# powerSMALL_smaller_OUT_GND.net
KiCad netlist of a schematic drawn in EAGLE
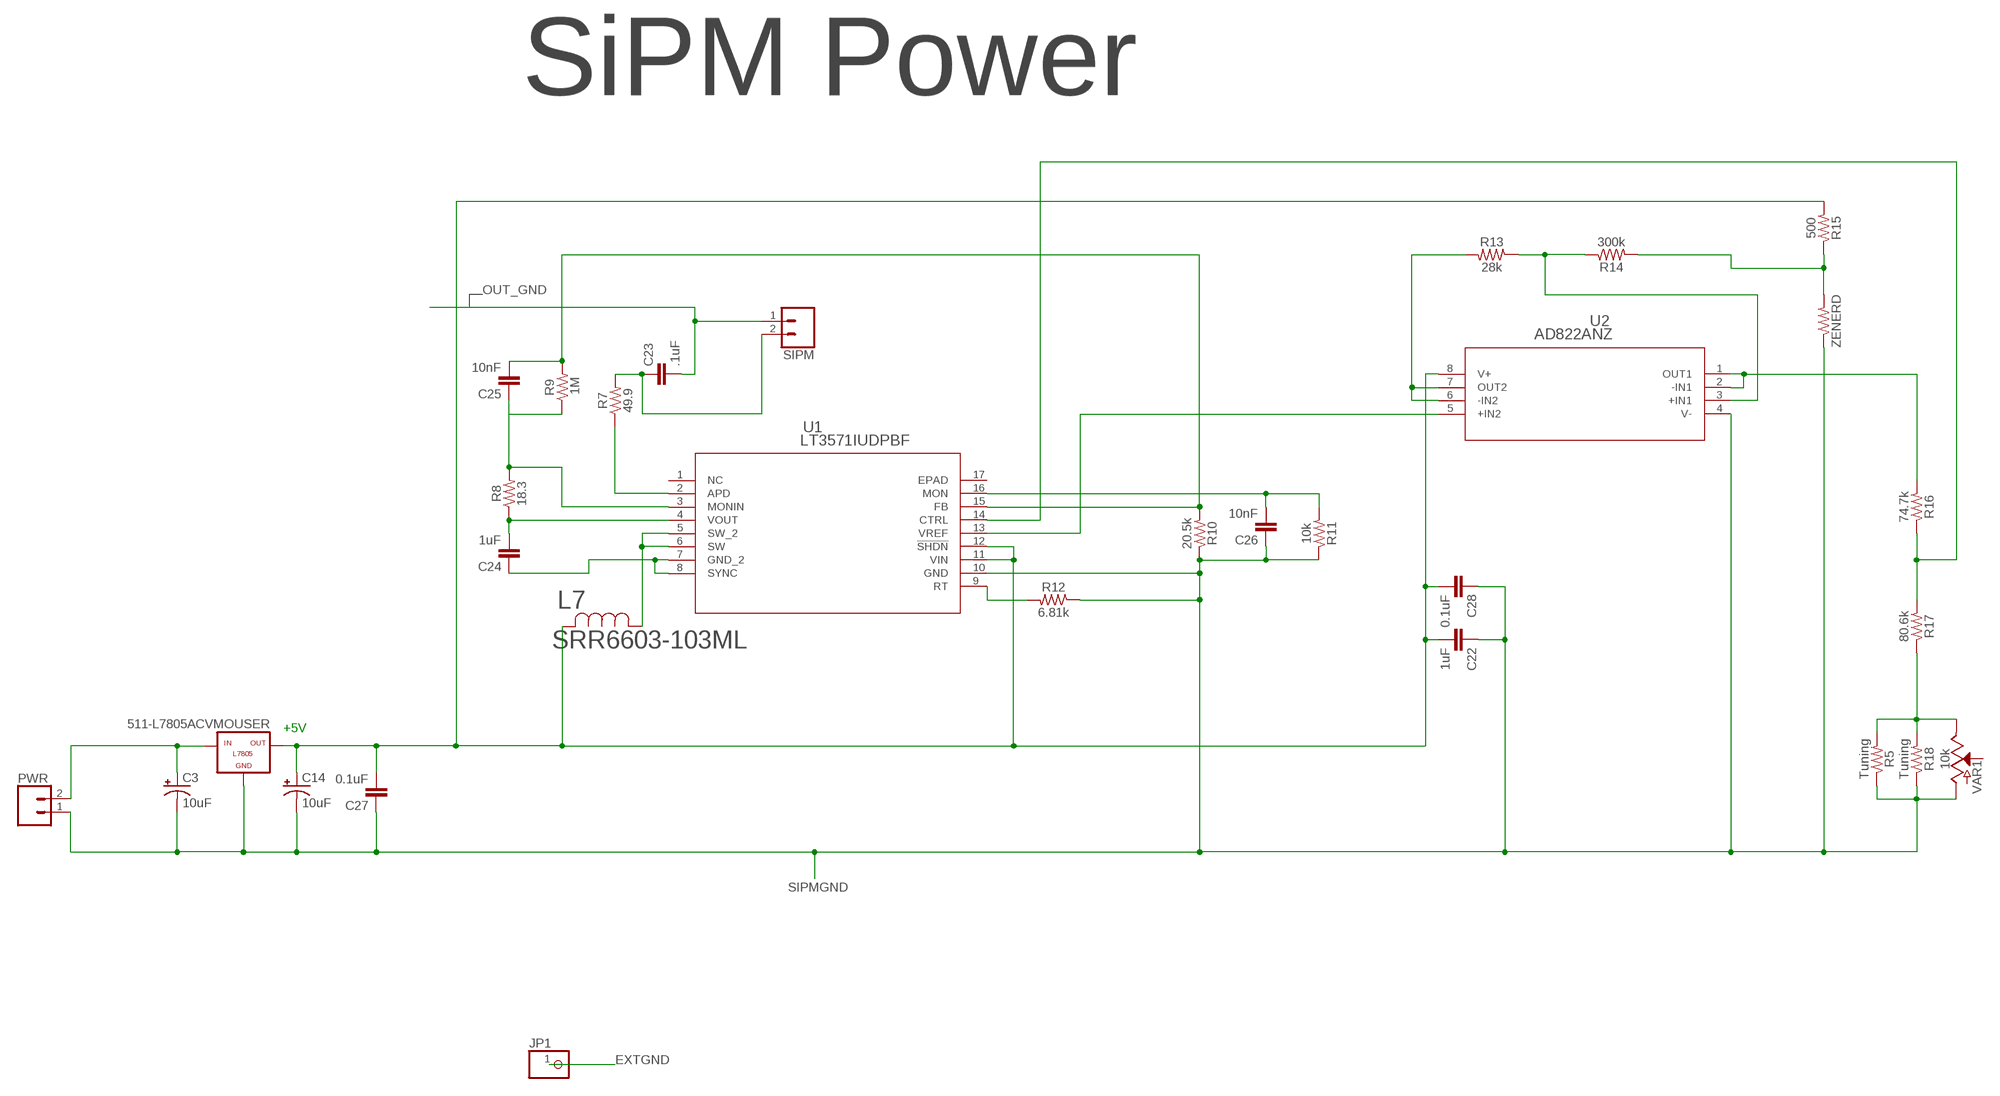
[diagram p0: schematic, sheet 1, part 1 of 2]
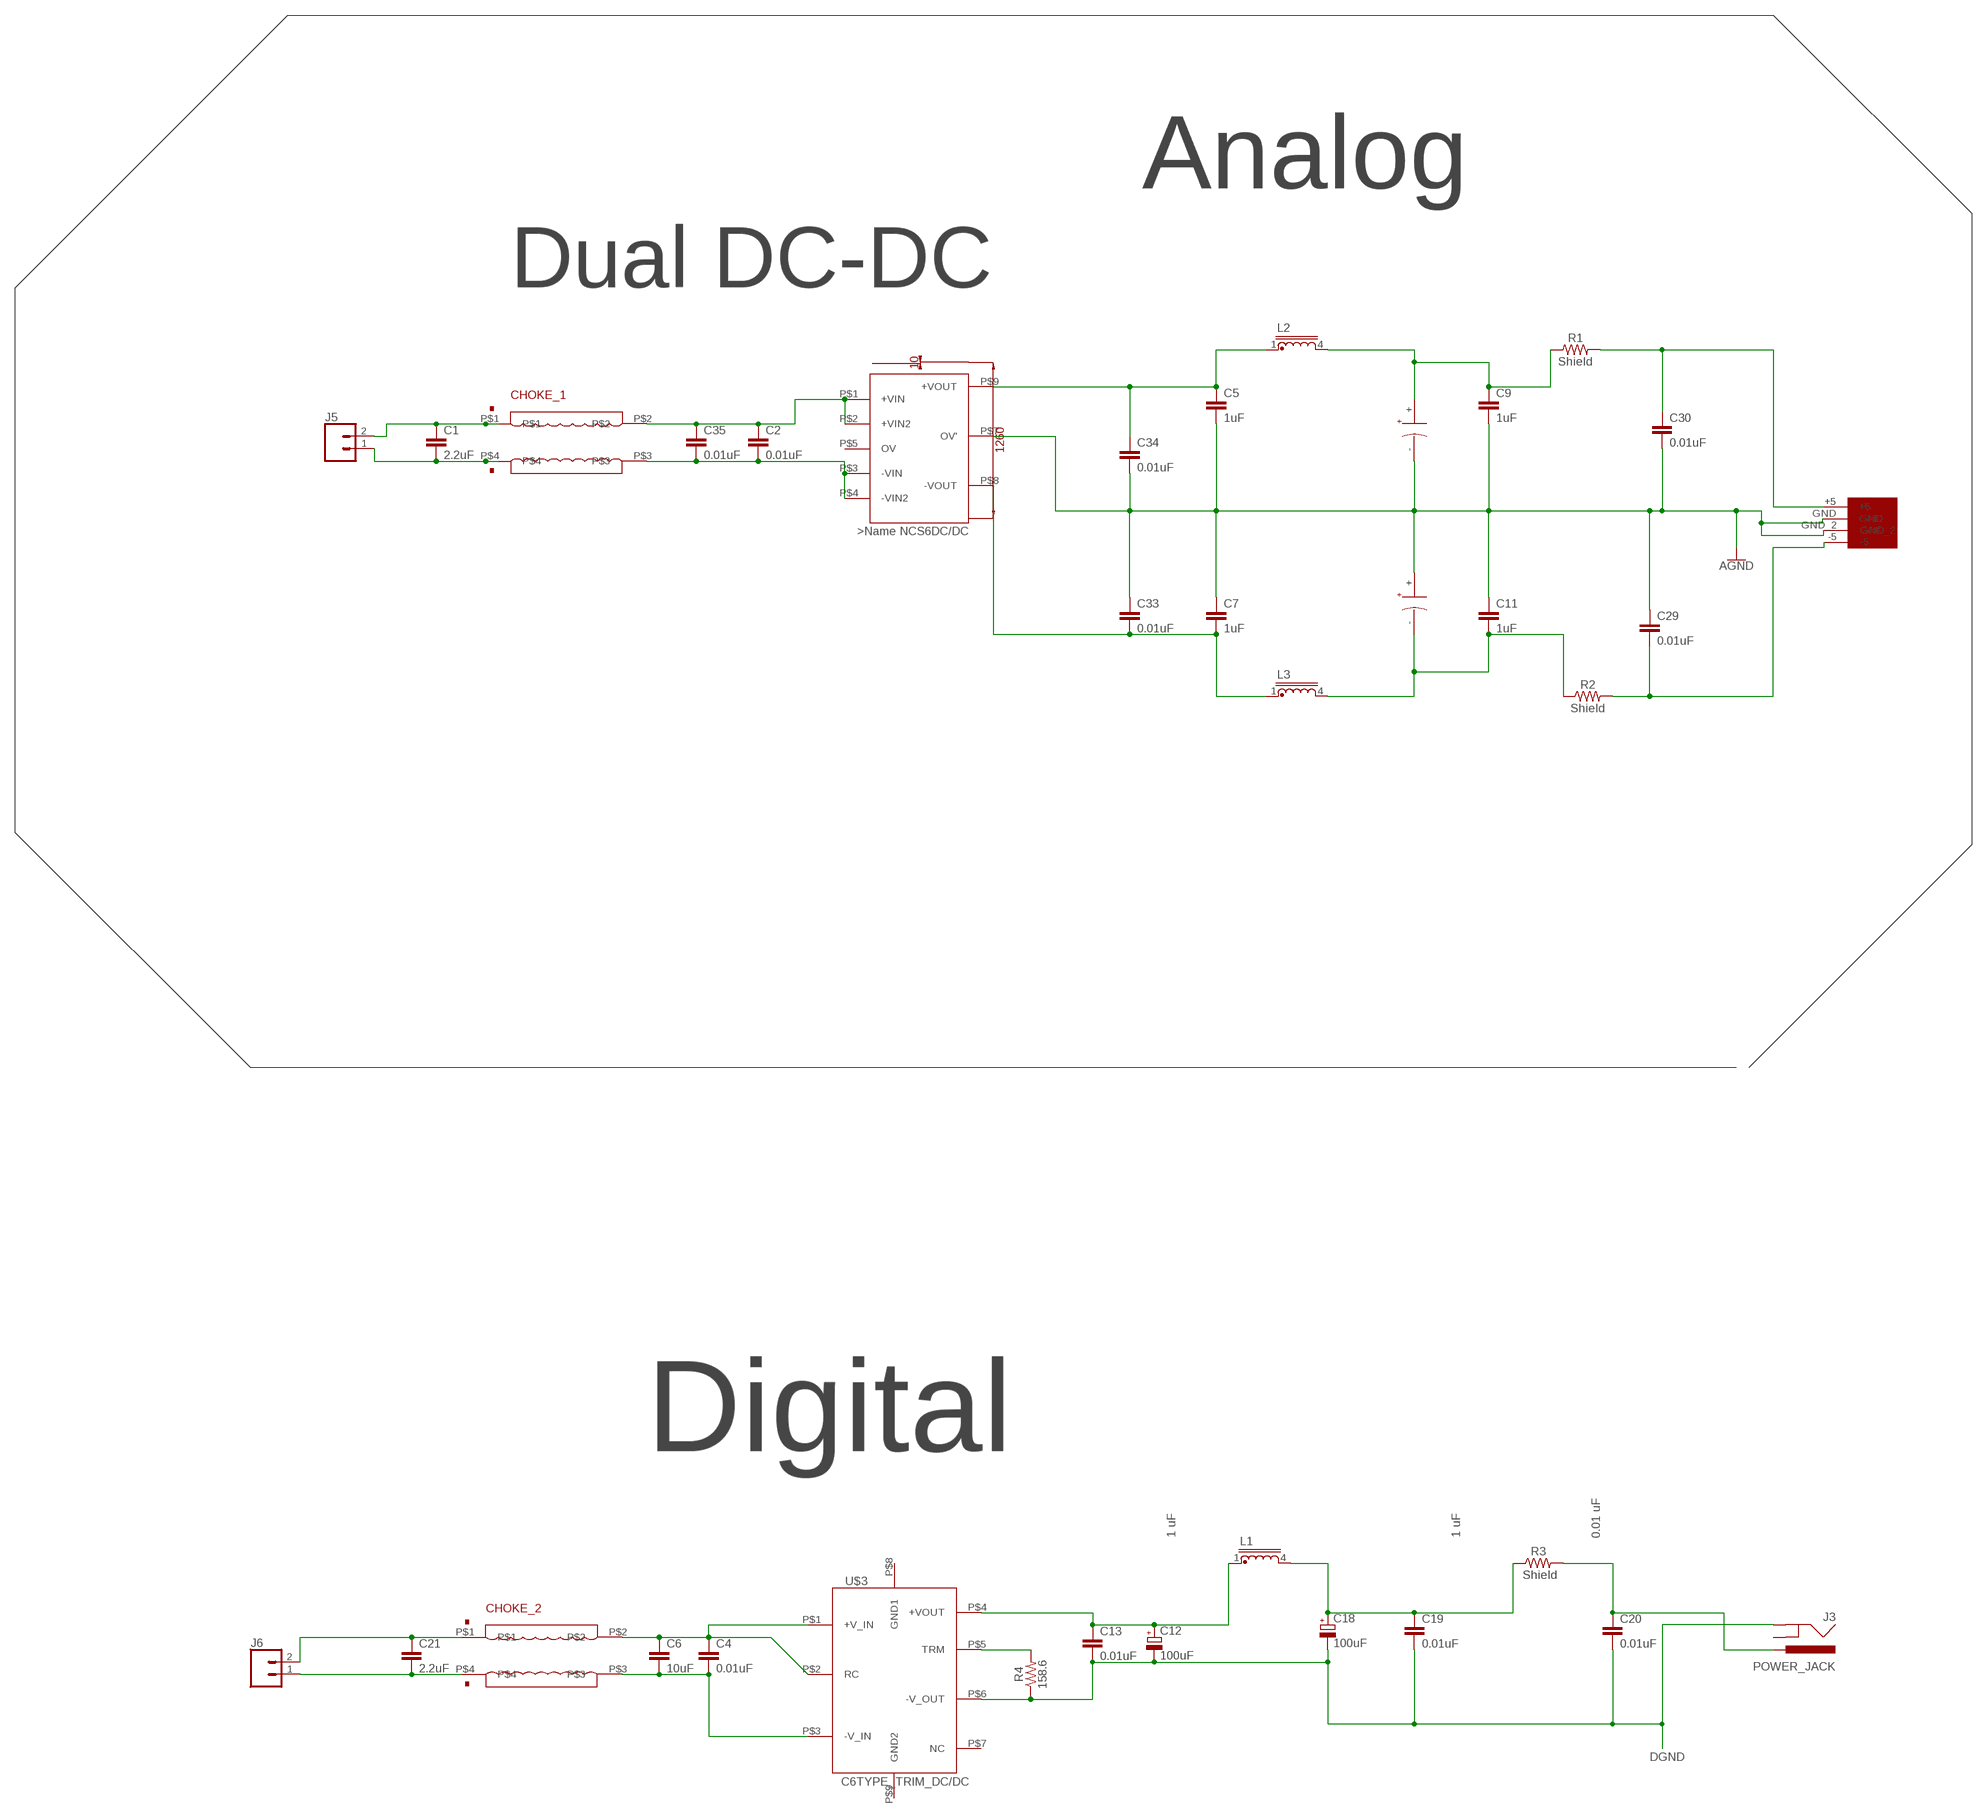
[diagram p1: schematic, sheet 1, part 2 of 2]

(export (version "E")
  (design (tool "Eeschema 10.0.6"))
  (components
    (comp (ref "511-L7805ACVMOUSER")
      (value "-L7805")
      (footprint "eagle-import:L7805")
      (libsource (lib "eagle-import") (part "-L7805"))
    )
    (comp (ref "C1")
      (value "2.2uF")
      (footprint "eagle-import:C050-024X044")
      (libsource (lib "eagle-import") (part "C-EU050-024X044"))
    )
    (comp (ref "C2")
      (value "0.01uF")
      (footprint "eagle-import:C025-025X050")
      (libsource (lib "eagle-import") (part "C-EU025-025X050"))
    )
    (comp (ref "C3")
      (value "10uF")
      (footprint "eagle-import:T_3528-12R")
      (libsource (lib "eagle-import") (part "CPOL-USB/3528-21R"))
    )
    (comp (ref "C4")
      (value "0.01uF")
      (footprint "eagle-import:C025-025X050")
      (libsource (lib "eagle-import") (part "C-EU025-025X050"))
    )
    (comp (ref "C5")
      (value "1uF")
      (footprint "eagle-import:C025-025X050")
      (libsource (lib "eagle-import") (part "C-EU025-025X050"))
    )
    (comp (ref "C6")
      (value "10uF")
      (footprint "eagle-import:C025-025X050")
      (libsource (lib "eagle-import") (part "C-EU025-025X050"))
    )
    (comp (ref "C7")
      (value "1uF")
      (footprint "eagle-import:C025-025X050")
      (libsource (lib "eagle-import") (part "C-EU025-025X050"))
    )
    (comp (ref "C8")
      (value "150uF")
      (footprint "eagle-import:399-3567-ND150UF")
      (libsource (lib "eagle-import") (part "399-4567-ND"))
    )
    (comp (ref "C9")
      (value "1uF")
      (footprint "eagle-import:C025-025X050")
      (libsource (lib "eagle-import") (part "C-EU025-025X050"))
    )
    (comp (ref "C10")
      (value "150uF")
      (footprint "eagle-import:399-3567-ND150UF")
      (libsource (lib "eagle-import") (part "399-4567-ND"))
    )
    (comp (ref "C11")
      (value "1uF")
      (footprint "eagle-import:C025-025X050")
      (libsource (lib "eagle-import") (part "C-EU025-025X050"))
    )
    (comp (ref "C12")
      (value "100uF")
      (footprint "eagle-import:C_6032-28R")
      (libsource (lib "eagle-import") (part "CPOL-EUC/6032-28R"))
    )
    (comp (ref "C13")
      (value "0.01uF")
      (footprint "eagle-import:C025-025X050")
      (libsource (lib "eagle-import") (part "C-EU025-025X050"))
    )
    (comp (ref "C14")
      (value "10uF")
      (footprint "eagle-import:T_3528-12R")
      (libsource (lib "eagle-import") (part "CPOL-USB/3528-21R"))
    )
    (comp (ref "C18")
      (value "100uF")
      (footprint "eagle-import:C_6032-28R")
      (fields (field (name "SPICEPREFIX") "C"))
      (libsource (lib "eagle-import") (part "CPOL-EUC/6032-28R"))
    )
    (comp (ref "C19")
      (value "0.01uF")
      (footprint "eagle-import:C025-025X050")
      (libsource (lib "eagle-import") (part "C-EU025-025X050"))
    )
    (comp (ref "C20")
      (value "0.01uF")
      (footprint "eagle-import:C025-025X050")
      (libsource (lib "eagle-import") (part "C-EU025-025X050"))
    )
    (comp (ref "C21")
      (value "2.2uF")
      (footprint "eagle-import:C050-024X044")
      (libsource (lib "eagle-import") (part "C-EU050-024X044"))
    )
    (comp (ref "C22")
      (value "1uF")
      (footprint "eagle-import:C025-025X050")
      (libsource (lib "eagle-import") (part "C-EU025-025X050"))
    )
    (comp (ref "C23")
      (value ".1uF")
      (footprint "eagle-import:C2.5-2")
      (libsource (lib "eagle-import") (part "C2.5/2"))
    )
    (comp (ref "C24")
      (value "1uF")
      (footprint "eagle-import:C025-025X050")
      (libsource (lib "eagle-import") (part "C-EU025-025X050"))
    )
    (comp (ref "C25")
      (value "10nF")
      (footprint "eagle-import:C2.5-2")
      (libsource (lib "eagle-import") (part "C2.5/2"))
    )
    (comp (ref "C26")
      (value "10nF")
      (footprint "eagle-import:C2.5-2")
      (libsource (lib "eagle-import") (part "C2.5/2"))
    )
    (comp (ref "C27")
      (value "0.1uF")
      (footprint "eagle-import:C2.5-2")
      (libsource (lib "eagle-import") (part "C2.5/2"))
    )
    (comp (ref "C28")
      (value "0.1uF")
      (footprint "eagle-import:C2.5-2")
      (libsource (lib "eagle-import") (part "C2.5/2"))
    )
    (comp (ref "C29")
      (value "0.01uF")
      (footprint "eagle-import:C0603")
      (libsource (lib "eagle-import") (part "C-EUC0603"))
    )
    (comp (ref "C30")
      (value "0.01uF")
      (footprint "eagle-import:C0603")
      (libsource (lib "eagle-import") (part "C-EUC0603"))
    )
    (comp (ref "C33")
      (value "0.01uF")
      (footprint "eagle-import:C0603")
      (libsource (lib "eagle-import") (part "C-EUC0603"))
    )
    (comp (ref "C34")
      (value "0.01uF")
      (footprint "eagle-import:C0603")
      (libsource (lib "eagle-import") (part "C-EUC0603"))
    )
    (comp (ref "C35")
      (value "0.01uF")
      (footprint "eagle-import:C0603")
      (libsource (lib "eagle-import") (part "C-EUC0603"))
    )
    (comp (ref "CHOKE_1")
      (value "DN4730-ND")
      (footprint "eagle-import:DN4730-ND")
      (libsource (lib "eagle-import") (part "DN4730-ND"))
    )
    (comp (ref "CHOKE_2")
      (value "DN4730-ND")
      (footprint "eagle-import:DN4730-ND")
      (libsource (lib "eagle-import") (part "DN4730-ND"))
    )
    (comp (ref "J3")
      (value "POWER_JACK")
      (footprint "eagle-import:POWER_JACK_PTH")
      (libsource (lib "eagle-import") (part "POWER_JACK"))
    )
    (comp (ref "J5")
      (value "CONN_02PTH4")
      (footprint "eagle-import:1X02_XTRA_BIG")
      (libsource (lib "eagle-import") (part "CONN_02PTH4"))
    )
    (comp (ref "J6")
      (value "CONN_02PTH4")
      (footprint "eagle-import:1X02_XTRA_BIG")
      (libsource (lib "eagle-import") (part "CONN_02PTH4"))
    )
    (comp (ref "JP1")
      (value "PINHD-1X1")
      (footprint "eagle-import:1X01")
      (libsource (lib "eagle-import") (part "PINHD-1X1"))
    )
    (comp (ref "L1")
      (value "U15-CHOKE")
      (footprint "eagle-import:U15CHOKE")
      (libsource (lib "eagle-import") (part "U15-CHOKE"))
    )
    (comp (ref "L2")
      (value "U15-CHOKE")
      (footprint "eagle-import:U15CHOKE")
      (libsource (lib "eagle-import") (part "U15-CHOKE"))
    )
    (comp (ref "L3")
      (value "U15-CHOKE")
      (footprint "eagle-import:U15CHOKE")
      (libsource (lib "eagle-import") (part "U15-CHOKE"))
    )
    (comp (ref "L7")
      (value "SRR6603-103ML")
      (footprint "eagle-import:IND_BOURNS_SRR6603")
      (fields (field (name "MANUFACTURER_PART_NUMBER") "SRR6603103ML"))
      (libsource (lib "eagle-import") (part "SRR6603-103ML"))
    )
    (comp (ref "PWR")
      (value "CONN_02PTH4")
      (footprint "eagle-import:1X02_XTRA_BIG")
      (libsource (lib "eagle-import") (part "CONN_02PTH4"))
    )
    (comp (ref "PWR_JACK")
      (value "WM403_NDPOWER_JACK")
      (footprint "eagle-import:WM4302-ND")
      (libsource (lib "eagle-import") (part "WM403_NDPOWER_JACK"))
    )
    (comp (ref "R1")
      (value "Shield")
      (footprint "eagle-import:AXIAL-0.3")
      (libsource (lib "eagle-import") (part "RESISTORAXIAL-0.3"))
    )
    (comp (ref "R2")
      (value "Shield")
      (footprint "eagle-import:AXIAL-0.3")
      (libsource (lib "eagle-import") (part "RESISTORAXIAL-0.3"))
    )
    (comp (ref "R3")
      (value "Shield")
      (footprint "eagle-import:AXIAL-0.3")
      (libsource (lib "eagle-import") (part "RESISTORAXIAL-0.3"))
    )
    (comp (ref "R4")
      (value "158.6")
      (footprint "eagle-import:AXIAL-0.3")
      (libsource (lib "eagle-import") (part "RESISTORAXIAL-0.3"))
    )
    (comp (ref "R5")
      (value "Tuning")
      (footprint "eagle-import:AXIAL-0.3")
      (libsource (lib "eagle-import") (part "RESISTORAXIAL-0.3"))
    )
    (comp (ref "R7")
      (value "49.9")
      (footprint "eagle-import:AXIAL-0.3")
      (libsource (lib "eagle-import") (part "RESISTORAXIAL-0.3"))
    )
    (comp (ref "R8")
      (value "18.3")
      (footprint "eagle-import:AXIAL-0.3")
      (libsource (lib "eagle-import") (part "RESISTORAXIAL-0.3"))
    )
    (comp (ref "R9")
      (value "1M")
      (footprint "eagle-import:AXIAL-0.3")
      (libsource (lib "eagle-import") (part "RESISTORAXIAL-0.3"))
    )
    (comp (ref "R10")
      (value "20.5k")
      (footprint "eagle-import:AXIAL-0.3")
      (libsource (lib "eagle-import") (part "RESISTORAXIAL-0.3"))
    )
    (comp (ref "R11")
      (value "10k")
      (footprint "eagle-import:AXIAL-0.3")
      (libsource (lib "eagle-import") (part "10KOHM-HORIZ-1/4W-1%"))
    )
    (comp (ref "R12")
      (value "6.81k")
      (footprint "eagle-import:AXIAL-0.3")
      (libsource (lib "eagle-import") (part "RESISTORAXIAL-0.3"))
    )
    (comp (ref "R13")
      (value "28k")
      (footprint "eagle-import:AXIAL-0.3")
      (libsource (lib "eagle-import") (part "RESISTORAXIAL-0.3"))
    )
    (comp (ref "R14")
      (value "300k")
      (footprint "eagle-import:AXIAL-0.3")
      (libsource (lib "eagle-import") (part "RESISTORAXIAL-0.3"))
    )
    (comp (ref "R15")
      (value "500")
      (footprint "eagle-import:AXIAL-0.3")
      (libsource (lib "eagle-import") (part "RESISTORAXIAL-0.3"))
    )
    (comp (ref "R16")
      (value "74.7k")
      (footprint "eagle-import:AXIAL-0.3")
      (libsource (lib "eagle-import") (part "RESISTORAXIAL-0.3"))
    )
    (comp (ref "R17")
      (value "80.6k")
      (footprint "eagle-import:AXIAL-0.3")
      (libsource (lib "eagle-import") (part "RESISTORAXIAL-0.3"))
    )
    (comp (ref "R18")
      (value "Tuning")
      (footprint "eagle-import:AXIAL-0.3")
      (libsource (lib "eagle-import") (part "RESISTORAXIAL-0.3"))
    )
    (comp (ref "SIPM")
      (value "CONN_02PTH4")
      (footprint "eagle-import:1X02_XTRA_BIG")
      (libsource (lib "eagle-import") (part "CONN_02PTH4"))
    )
    (comp (ref "U$1")
      (value "NCS6D1205")
      (footprint "eagle-import:NCS6D1205C")
      (libsource (lib "eagle-import") (part "NCS6D1205"))
    )
    (comp (ref "U$3")
      (value "C6TYPE_TRIM_DC/DC")
      (footprint "eagle-import:CONV_DC_DC_6W_SNGL_C6TYPE")
      (libsource (lib "eagle-import") (part "C6TYPE_TRIM_DC/DC"))
    )
    (comp (ref "U1")
      (value "LT3571IUDPBF")
      (footprint "eagle-import:QFN-16_UD")
      (fields (field (name "MANUFACTURER_PART_NUMBER") "LT3571IUD#PBF"))
      (libsource (lib "eagle-import") (part "LT3571IUDPBF"))
    )
    (comp (ref "U2")
      (value "AD822ANZ")
      (footprint "eagle-import:N_8")
      (libsource (lib "eagle-import") (part "AD822ANZ"))
    )
    (comp (ref "VAR1")
      (value "10k")
      (footprint "eagle-import:POT-PTH-ALPS")
      (libsource (lib "eagle-import") (part "POTENTIOMETER-PTH-9MM-1/20W-20%"))
    )
    (comp (ref "ZENERD")
      (value "RESISTORAXIAL-0.3")
      (footprint "eagle-import:AXIAL-0.3")
      (libsource (lib "eagle-import") (part "RESISTORAXIAL-0.3"))
    )
  )
  (nets
    (net (code "1") (name "/DGND") (class "Default")
      (node (ref "C12") (pin "-") (pinfunction "-_-") (pintype "passive"))
      (node (ref "C13") (pin "2") (pinfunction "2_2") (pintype "passive"))
      (node (ref "C18") (pin "-") (pinfunction "-_-") (pintype "passive"))
      (node (ref "C19") (pin "2") (pinfunction "2_2") (pintype "passive"))
      (node (ref "C20") (pin "2") (pinfunction "2_2") (pintype "passive"))
      (node (ref "J3") (pin "GND") (pinfunction "GND_GND") (pintype "bidirectional"))
      (node (ref "R4") (pin "P$1") (pinfunction "1_P$1") (pintype "passive"))
      (node (ref "U$3") (pin "P$6") (pinfunction "-V_OUT_P$6") (pintype "bidirectional"))
    )
    (net (code "2") (name "/EXTGND") (class "Default")
      (node (ref "JP1") (pin "1") (pinfunction "1_1") (pintype "passive"))
    )
    (net (code "3") (name "/OUT_GND") (class "Default")
      (node (ref "C23") (pin "2") (pinfunction "2_2") (pintype "passive"))
      (node (ref "SIPM") (pin "1") (pinfunction "1_1") (pintype "passive"))
    )
    (net (code "4") (name "/SIPMGND") (class "Default")
      (node (ref "511-L7805ACVMOUSER") (pin "GND") (pinfunction "GND_GND") (pintype "input"))
      (node (ref "C14") (pin "-") (pinfunction "-_-") (pintype "passive"))
      (node (ref "C22") (pin "1") (pinfunction "1_1") (pintype "passive"))
      (node (ref "C26") (pin "1") (pinfunction "1_1") (pintype "passive"))
      (node (ref "C27") (pin "1") (pinfunction "1_1") (pintype "passive"))
      (node (ref "C28") (pin "1") (pinfunction "1_1") (pintype "passive"))
      (node (ref "C3") (pin "-") (pinfunction "-_-") (pintype "passive"))
      (node (ref "PWR") (pin "1") (pinfunction "1_1") (pintype "passive"))
      (node (ref "R10") (pin "P$1") (pinfunction "1_P$1") (pintype "passive"))
      (node (ref "R11") (pin "P$1") (pinfunction "1_P$1") (pintype "passive"))
      (node (ref "R12") (pin "P$1") (pinfunction "1_P$1") (pintype "passive"))
      (node (ref "R18") (pin "P$1") (pinfunction "1_P$1") (pintype "passive"))
      (node (ref "R5") (pin "P$1") (pinfunction "1_P$1") (pintype "passive"))
      (node (ref "U1") (pin "10") (pinfunction "GND_10") (pintype "power_in"))
      (node (ref "U2") (pin "4") (pinfunction "V-_4") (pintype "power_in"))
      (node (ref "VAR1") (pin "P$3") (pinfunction "A_P$3") (pintype "passive"))
      (node (ref "ZENERD") (pin "P$1") (pinfunction "1_P$1") (pintype "passive"))
    )
    (net (code "5") (name "AGND") (class "Default")
      (node (ref "C10") (pin "+") (pinfunction "P_+") (pintype "bidirectional"))
      (node (ref "C11") (pin "1") (pinfunction "1_1") (pintype "passive"))
      (node (ref "C29") (pin "1") (pinfunction "1_1") (pintype "passive"))
      (node (ref "C30") (pin "2") (pinfunction "2_2") (pintype "passive"))
      (node (ref "C33") (pin "1") (pinfunction "1_1") (pintype "passive"))
      (node (ref "C34") (pin "2") (pinfunction "2_2") (pintype "passive"))
      (node (ref "C5") (pin "2") (pinfunction "2_2") (pintype "passive"))
      (node (ref "C7") (pin "1") (pinfunction "1_1") (pintype "passive"))
      (node (ref "C8") (pin "-") (pinfunction "N_-") (pintype "bidirectional"))
      (node (ref "C9") (pin "2") (pinfunction "2_2") (pintype "passive"))
      (node (ref "PWR_JACK") (pin "GND") (pinfunction "GND_GND") (pintype "bidirectional"))
      (node (ref "PWR_JACK") (pin "GND_2") (pinfunction "GND_2_GND_2") (pintype "bidirectional"))
      (node (ref "U$1") (pin "P$7") (pinfunction "OV'_P$7") (pintype "bidirectional"))
    )
    (net (code "6") (name "Net-(511-L7805ACVMOUSER-PadIN)") (class "Default")
      (node (ref "511-L7805ACVMOUSER") (pin "IN") (pinfunction "IN_IN") (pintype "input"))
      (node (ref "C3") (pin "+") (pinfunction "+_+") (pintype "passive"))
      (node (ref "PWR") (pin "2") (pinfunction "2_2") (pintype "passive"))
    )
    (net (code "7") (name "Net-(C1-Pad1)") (class "Default")
      (node (ref "C1") (pin "1") (pinfunction "1_1") (pintype "passive"))
      (node (ref "CHOKE_1") (pin "P$1") (pinfunction "P$1_P$1") (pintype "bidirectional"))
      (node (ref "J5") (pin "2") (pinfunction "2_2") (pintype "passive"))
    )
    (net (code "8") (name "Net-(C1-Pad2)") (class "Default")
      (node (ref "C1") (pin "2") (pinfunction "2_2") (pintype "passive"))
      (node (ref "CHOKE_1") (pin "P$4") (pinfunction "P$4_P$4") (pintype "bidirectional"))
      (node (ref "J5") (pin "1") (pinfunction "1_1") (pintype "passive"))
    )
    (net (code "9") (name "Net-(C8-P)") (class "Default")
      (node (ref "C8") (pin "+") (pinfunction "P_+") (pintype "bidirectional"))
      (node (ref "C9") (pin "1") (pinfunction "1_1") (pintype "passive"))
      (node (ref "L2") (pin "4") (pinfunction "4_4") (pintype "passive"))
      (node (ref "R1") (pin "P$1") (pinfunction "1_P$1") (pintype "passive"))
    )
    (net (code "10") (name "Net-(C10-N)") (class "Default")
      (node (ref "C10") (pin "-") (pinfunction "N_-") (pintype "bidirectional"))
      (node (ref "C11") (pin "2") (pinfunction "2_2") (pintype "passive"))
      (node (ref "L3") (pin "4") (pinfunction "4_4") (pintype "passive"))
      (node (ref "R2") (pin "P$1") (pinfunction "1_P$1") (pintype "passive"))
    )
    (net (code "11") (name "Net-(C21-Pad1)") (class "Default")
      (node (ref "C21") (pin "1") (pinfunction "1_1") (pintype "passive"))
      (node (ref "CHOKE_2") (pin "P$1") (pinfunction "P$1_P$1") (pintype "bidirectional"))
      (node (ref "J6") (pin "2") (pinfunction "2_2") (pintype "passive"))
    )
    (net (code "12") (name "Net-(C21-Pad2)") (class "Default")
      (node (ref "C21") (pin "2") (pinfunction "2_2") (pintype "passive"))
      (node (ref "CHOKE_2") (pin "P$4") (pinfunction "P$4_P$4") (pintype "bidirectional"))
      (node (ref "J6") (pin "1") (pinfunction "1_1") (pintype "passive"))
    )
    (net (code "13") (name "Net-(R1-2)") (class "Default")
      (node (ref "C30") (pin "1") (pinfunction "1_1") (pintype "passive"))
      (node (ref "PWR_JACK") (pin "+5") (pinfunction "+5_+5") (pintype "bidirectional"))
      (node (ref "R1") (pin "P$2") (pinfunction "2_P$2") (pintype "passive"))
    )
    (net (code "14") (name "Net-(R2-2)") (class "Default")
      (node (ref "C29") (pin "2") (pinfunction "2_2") (pintype "passive"))
      (node (ref "PWR_JACK") (pin "-5") (pinfunction "-5_-5") (pintype "bidirectional"))
      (node (ref "R2") (pin "P$2") (pinfunction "2_P$2") (pintype "passive"))
    )
    (net (code "15") (name "Net-(R3-1)") (class "Default")
      (node (ref "C18") (pin "+") (pinfunction "+_+") (pintype "passive"))
      (node (ref "C19") (pin "1") (pinfunction "1_1") (pintype "passive"))
      (node (ref "L1") (pin "4") (pinfunction "4_4") (pintype "passive"))
      (node (ref "R3") (pin "P$1") (pinfunction "1_P$1") (pintype "passive"))
    )
    (net (code "16") (name "Net-(R3-2)") (class "Default")
      (node (ref "C20") (pin "1") (pinfunction "1_1") (pintype "passive"))
      (node (ref "J3") (pin "PWR") (pinfunction "PWR_PWR") (pintype "bidirectional"))
      (node (ref "R3") (pin "P$2") (pinfunction "2_P$2") (pintype "passive"))
    )
    (net (code "17") (name "Net-(R4-2)") (class "Default")
      (node (ref "R4") (pin "P$2") (pinfunction "2_P$2") (pintype "passive"))
      (node (ref "U$3") (pin "P$5") (pinfunction "TRM_P$5") (pintype "bidirectional"))
    )
    (net (code "18") (name "Net-(R7-1)") (class "Default")
      (node (ref "R7") (pin "P$1") (pinfunction "1_P$1") (pintype "passive"))
      (node (ref "U1") (pin "2") (pinfunction "APD_2") (pintype "passive"))
    )
    (net (code "19") (name "Net-(R7-2)") (class "Default")
      (node (ref "C23") (pin "1") (pinfunction "1_1") (pintype "passive"))
      (node (ref "R7") (pin "P$2") (pinfunction "2_P$2") (pintype "passive"))
      (node (ref "SIPM") (pin "2") (pinfunction "2_2") (pintype "passive"))
    )
    (net (code "20") (name "Net-(R8-1)") (class "Default")
      (node (ref "C24") (pin "2") (pinfunction "2_2") (pintype "passive"))
      (node (ref "R8") (pin "P$1") (pinfunction "1_P$1") (pintype "passive"))
      (node (ref "U1") (pin "4") (pinfunction "VOUT_4") (pintype "output"))
    )
    (net (code "21") (name "Net-(R8-2)") (class "Default")
      (node (ref "C25") (pin "1") (pinfunction "1_1") (pintype "passive"))
      (node (ref "R8") (pin "P$2") (pinfunction "2_P$2") (pintype "passive"))
      (node (ref "R9") (pin "P$1") (pinfunction "1_P$1") (pintype "passive"))
      (node (ref "U1") (pin "3") (pinfunction "MONIN_3") (pintype "input"))
    )
    (net (code "22") (name "Net-(R10-2)") (class "Default")
      (node (ref "C25") (pin "2") (pinfunction "2_2") (pintype "passive"))
      (node (ref "R10") (pin "P$2") (pinfunction "2_P$2") (pintype "passive"))
      (node (ref "R9") (pin "P$2") (pinfunction "2_P$2") (pintype "passive"))
      (node (ref "U1") (pin "15") (pinfunction "FB_15") (pintype "output"))
    )
    (net (code "23") (name "Net-(R11-2)") (class "Default")
      (node (ref "C26") (pin "2") (pinfunction "2_2") (pintype "passive"))
      (node (ref "R11") (pin "P$2") (pinfunction "2_P$2") (pintype "passive"))
      (node (ref "U1") (pin "16") (pinfunction "MON_16") (pintype "output"))
    )
    (net (code "24") (name "Net-(R12-2)") (class "Default")
      (node (ref "R12") (pin "P$2") (pinfunction "2_P$2") (pintype "passive"))
      (node (ref "U1") (pin "9") (pinfunction "RT_9") (pintype "passive"))
    )
    (net (code "25") (name "Net-(R13-1)") (class "Default")
      (node (ref "R13") (pin "P$1") (pinfunction "1_P$1") (pintype "passive"))
      (node (ref "R14") (pin "P$1") (pinfunction "1_P$1") (pintype "passive"))
      (node (ref "U2") (pin "3") (pinfunction "+IN1_3") (pintype "passive"))
    )
    (net (code "26") (name "Net-(R13-2)") (class "Default")
      (node (ref "R13") (pin "P$2") (pinfunction "2_P$2") (pintype "passive"))
      (node (ref "U2") (pin "6") (pinfunction "-IN2_6") (pintype "passive"))
      (node (ref "U2") (pin "7") (pinfunction "OUT2_7") (pintype "passive"))
    )
    (net (code "27") (name "Net-(R14-2)") (class "Default")
      (node (ref "R14") (pin "P$2") (pinfunction "2_P$2") (pintype "passive"))
      (node (ref "R15") (pin "P$1") (pinfunction "1_P$1") (pintype "passive"))
      (node (ref "ZENERD") (pin "P$2") (pinfunction "2_P$2") (pintype "passive"))
    )
    (net (code "28") (name "Net-(R15-2)") (class "Default")
      (node (ref "511-L7805ACVMOUSER") (pin "OUT") (pinfunction "OUT_OUT") (pintype "passive"))
      (node (ref "C14") (pin "+") (pinfunction "+_+") (pintype "passive"))
      (node (ref "C22") (pin "2") (pinfunction "2_2") (pintype "passive"))
      (node (ref "C27") (pin "2") (pinfunction "2_2") (pintype "passive"))
      (node (ref "C28") (pin "2") (pinfunction "2_2") (pintype "passive"))
      (node (ref "L7") (pin "2") (pinfunction "2_2") (pintype "passive"))
      (node (ref "R15") (pin "P$2") (pinfunction "2_P$2") (pintype "passive"))
      (node (ref "U1") (pin "11") (pinfunction "VIN_11") (pintype "input"))
      (node (ref "U1") (pin "12") (pinfunction "~{SHDN}_12") (pintype "passive"))
      (node (ref "U2") (pin "8") (pinfunction "V+_8") (pintype "power_in"))
    )
    (net (code "29") (name "Net-(R16-1)") (class "Default")
      (node (ref "R16") (pin "P$1") (pinfunction "1_P$1") (pintype "passive"))
      (node (ref "R17") (pin "P$2") (pinfunction "2_P$2") (pintype "passive"))
      (node (ref "U1") (pin "14") (pinfunction "CTRL_14") (pintype "output"))
    )
    (net (code "30") (name "Net-(R16-2)") (class "Default")
      (node (ref "R16") (pin "P$2") (pinfunction "2_P$2") (pintype "passive"))
      (node (ref "U2") (pin "1") (pinfunction "OUT1_1") (pintype "passive"))
      (node (ref "U2") (pin "2") (pinfunction "-IN1_2") (pintype "passive"))
    )
    (net (code "31") (name "Net-(R17-1)") (class "Default")
      (node (ref "R17") (pin "P$1") (pinfunction "1_P$1") (pintype "passive"))
      (node (ref "R18") (pin "P$2") (pinfunction "2_P$2") (pintype "passive"))
      (node (ref "R5") (pin "P$2") (pinfunction "2_P$2") (pintype "passive"))
      (node (ref "VAR1") (pin "P$1") (pinfunction "E_P$1") (pintype "passive"))
    )
    (net (code "32") (name "Net-(U$1-+VIN)") (class "Default")
      (node (ref "C2") (pin "1") (pinfunction "1_1") (pintype "passive"))
      (node (ref "C35") (pin "1") (pinfunction "1_1") (pintype "passive"))
      (node (ref "CHOKE_1") (pin "P$2") (pinfunction "P$2_P$2") (pintype "bidirectional"))
      (node (ref "U$1") (pin "P$1") (pinfunction "+VIN_P$1") (pintype "power_in"))
      (node (ref "U$1") (pin "P$2") (pinfunction "+VIN2_P$2") (pintype "power_in"))
    )
    (net (code "33") (name "Net-(U$1-+VOUT)") (class "Default")
      (node (ref "C34") (pin "1") (pinfunction "1_1") (pintype "passive"))
      (node (ref "C5") (pin "1") (pinfunction "1_1") (pintype "passive"))
      (node (ref "L2") (pin "1") (pinfunction "1_1") (pintype "passive"))
      (node (ref "U$1") (pin "P$9") (pinfunction "+VOUT_P$9") (pintype "bidirectional"))
    )
    (net (code "34") (name "Net-(U$1--VIN)") (class "Default")
      (node (ref "C2") (pin "2") (pinfunction "2_2") (pintype "passive"))
      (node (ref "C35") (pin "2") (pinfunction "2_2") (pintype "passive"))
      (node (ref "CHOKE_1") (pin "P$3") (pinfunction "P$3_P$3") (pintype "bidirectional"))
      (node (ref "U$1") (pin "P$3") (pinfunction "-VIN_P$3") (pintype "bidirectional"))
      (node (ref "U$1") (pin "P$4") (pinfunction "-VIN2_P$4") (pintype "bidirectional"))
    )
    (net (code "35") (name "Net-(U$1--VOUT)") (class "Default")
      (node (ref "C33") (pin "2") (pinfunction "2_2") (pintype "passive"))
      (node (ref "C7") (pin "2") (pinfunction "2_2") (pintype "passive"))
      (node (ref "L3") (pin "1") (pinfunction "1_1") (pintype "passive"))
      (node (ref "U$1") (pin "P$8") (pinfunction "-VOUT_P$8") (pintype "bidirectional"))
    )
    (net (code "36") (name "Net-(U$3-+VOUT)") (class "Default")
      (node (ref "C12") (pin "+") (pinfunction "+_+") (pintype "passive"))
      (node (ref "C13") (pin "1") (pinfunction "1_1") (pintype "passive"))
      (node (ref "L1") (pin "1") (pinfunction "1_1") (pintype "passive"))
      (node (ref "U$3") (pin "P$4") (pinfunction "+VOUT_P$4") (pintype "bidirectional"))
    )
    (net (code "37") (name "Net-(U$3-+V_IN)") (class "Default")
      (node (ref "C4") (pin "1") (pinfunction "1_1") (pintype "passive"))
      (node (ref "C6") (pin "1") (pinfunction "1_1") (pintype "passive"))
      (node (ref "CHOKE_2") (pin "P$2") (pinfunction "P$2_P$2") (pintype "bidirectional"))
      (node (ref "U$3") (pin "P$1") (pinfunction "+V_IN_P$1") (pintype "bidirectional"))
      (node (ref "U$3") (pin "P$2") (pinfunction "RC_P$2") (pintype "bidirectional"))
    )
    (net (code "38") (name "Net-(U$3--V_IN)") (class "Default")
      (node (ref "C4") (pin "2") (pinfunction "2_2") (pintype "passive"))
      (node (ref "C6") (pin "2") (pinfunction "2_2") (pintype "passive"))
      (node (ref "CHOKE_2") (pin "P$3") (pinfunction "P$3_P$3") (pintype "bidirectional"))
      (node (ref "U$3") (pin "P$3") (pinfunction "-V_IN_P$3") (pintype "bidirectional"))
    )
    (net (code "39") (name "Net-(U1-GND_2)") (class "Default")
      (node (ref "C24") (pin "1") (pinfunction "1_1") (pintype "passive"))
      (node (ref "U1") (pin "7") (pinfunction "GND_2_7") (pintype "power_in"))
      (node (ref "U1") (pin "8") (pinfunction "SYNC_8") (pintype "passive"))
    )
    (net (code "40") (name "Net-(U1-SW)") (class "Default")
      (node (ref "L7") (pin "1") (pinfunction "1_1") (pintype "passive"))
      (node (ref "U1") (pin "5") (pinfunction "SW_2_5") (pintype "passive"))
      (node (ref "U1") (pin "6") (pinfunction "SW_6") (pintype "passive"))
    )
    (net (code "41") (name "Net-(U1-VREF)") (class "Default")
      (node (ref "U1") (pin "13") (pinfunction "VREF_13") (pintype "output"))
      (node (ref "U2") (pin "5") (pinfunction "+IN2_5") (pintype "passive"))
    )
    (net (code "42") (name "unconnected-(J3-PadGNDBREAK)") (class "Default")
      (node (ref "J3") (pin "GNDBREAK") (pinfunction "GNDBREAK_GNDBREAK") (pintype "bidirectional"))
    )
    (net (code "43") (name "unconnected-(U$1-OV-PadP$5)") (class "Default")
      (node (ref "U$1") (pin "P$5") (pinfunction "OV_P$5") (pintype "bidirectional"))
    )
    (net (code "44") (name "unconnected-(U$3-GND1-PadP$8)") (class "Default")
      (node (ref "U$3") (pin "P$8") (pinfunction "GND1_P$8") (pintype "bidirectional"))
    )
    (net (code "45") (name "unconnected-(U$3-GND2-PadP$9)") (class "Default")
      (node (ref "U$3") (pin "P$9") (pinfunction "GND2_P$9") (pintype "bidirectional"))
    )
    (net (code "46") (name "unconnected-(U$3-NC-PadP$7)") (class "Default")
      (node (ref "U$3") (pin "P$7") (pinfunction "NC_P$7") (pintype "bidirectional"))
    )
    (net (code "47") (name "unconnected-(U1-EPAD-Pad17)") (class "Default")
      (node (ref "U1") (pin "17") (pinfunction "EPAD_17") (pintype "passive"))
    )
    (net (code "48") (name "unconnected-(U1-NC-Pad1)") (class "Default")
      (node (ref "U1") (pin "1") (pinfunction "NC_1") (pintype "no_connect"))
    )
    (net (code "49") (name "unconnected-(VAR1-S-PadP$2)") (class "Default")
      (node (ref "VAR1") (pin "P$2") (pinfunction "S_P$2") (pintype "passive"))
    )
  )
)
